# PowerManagement_Base.net
KiCad netlist of a schematic drawn in Altium Designer
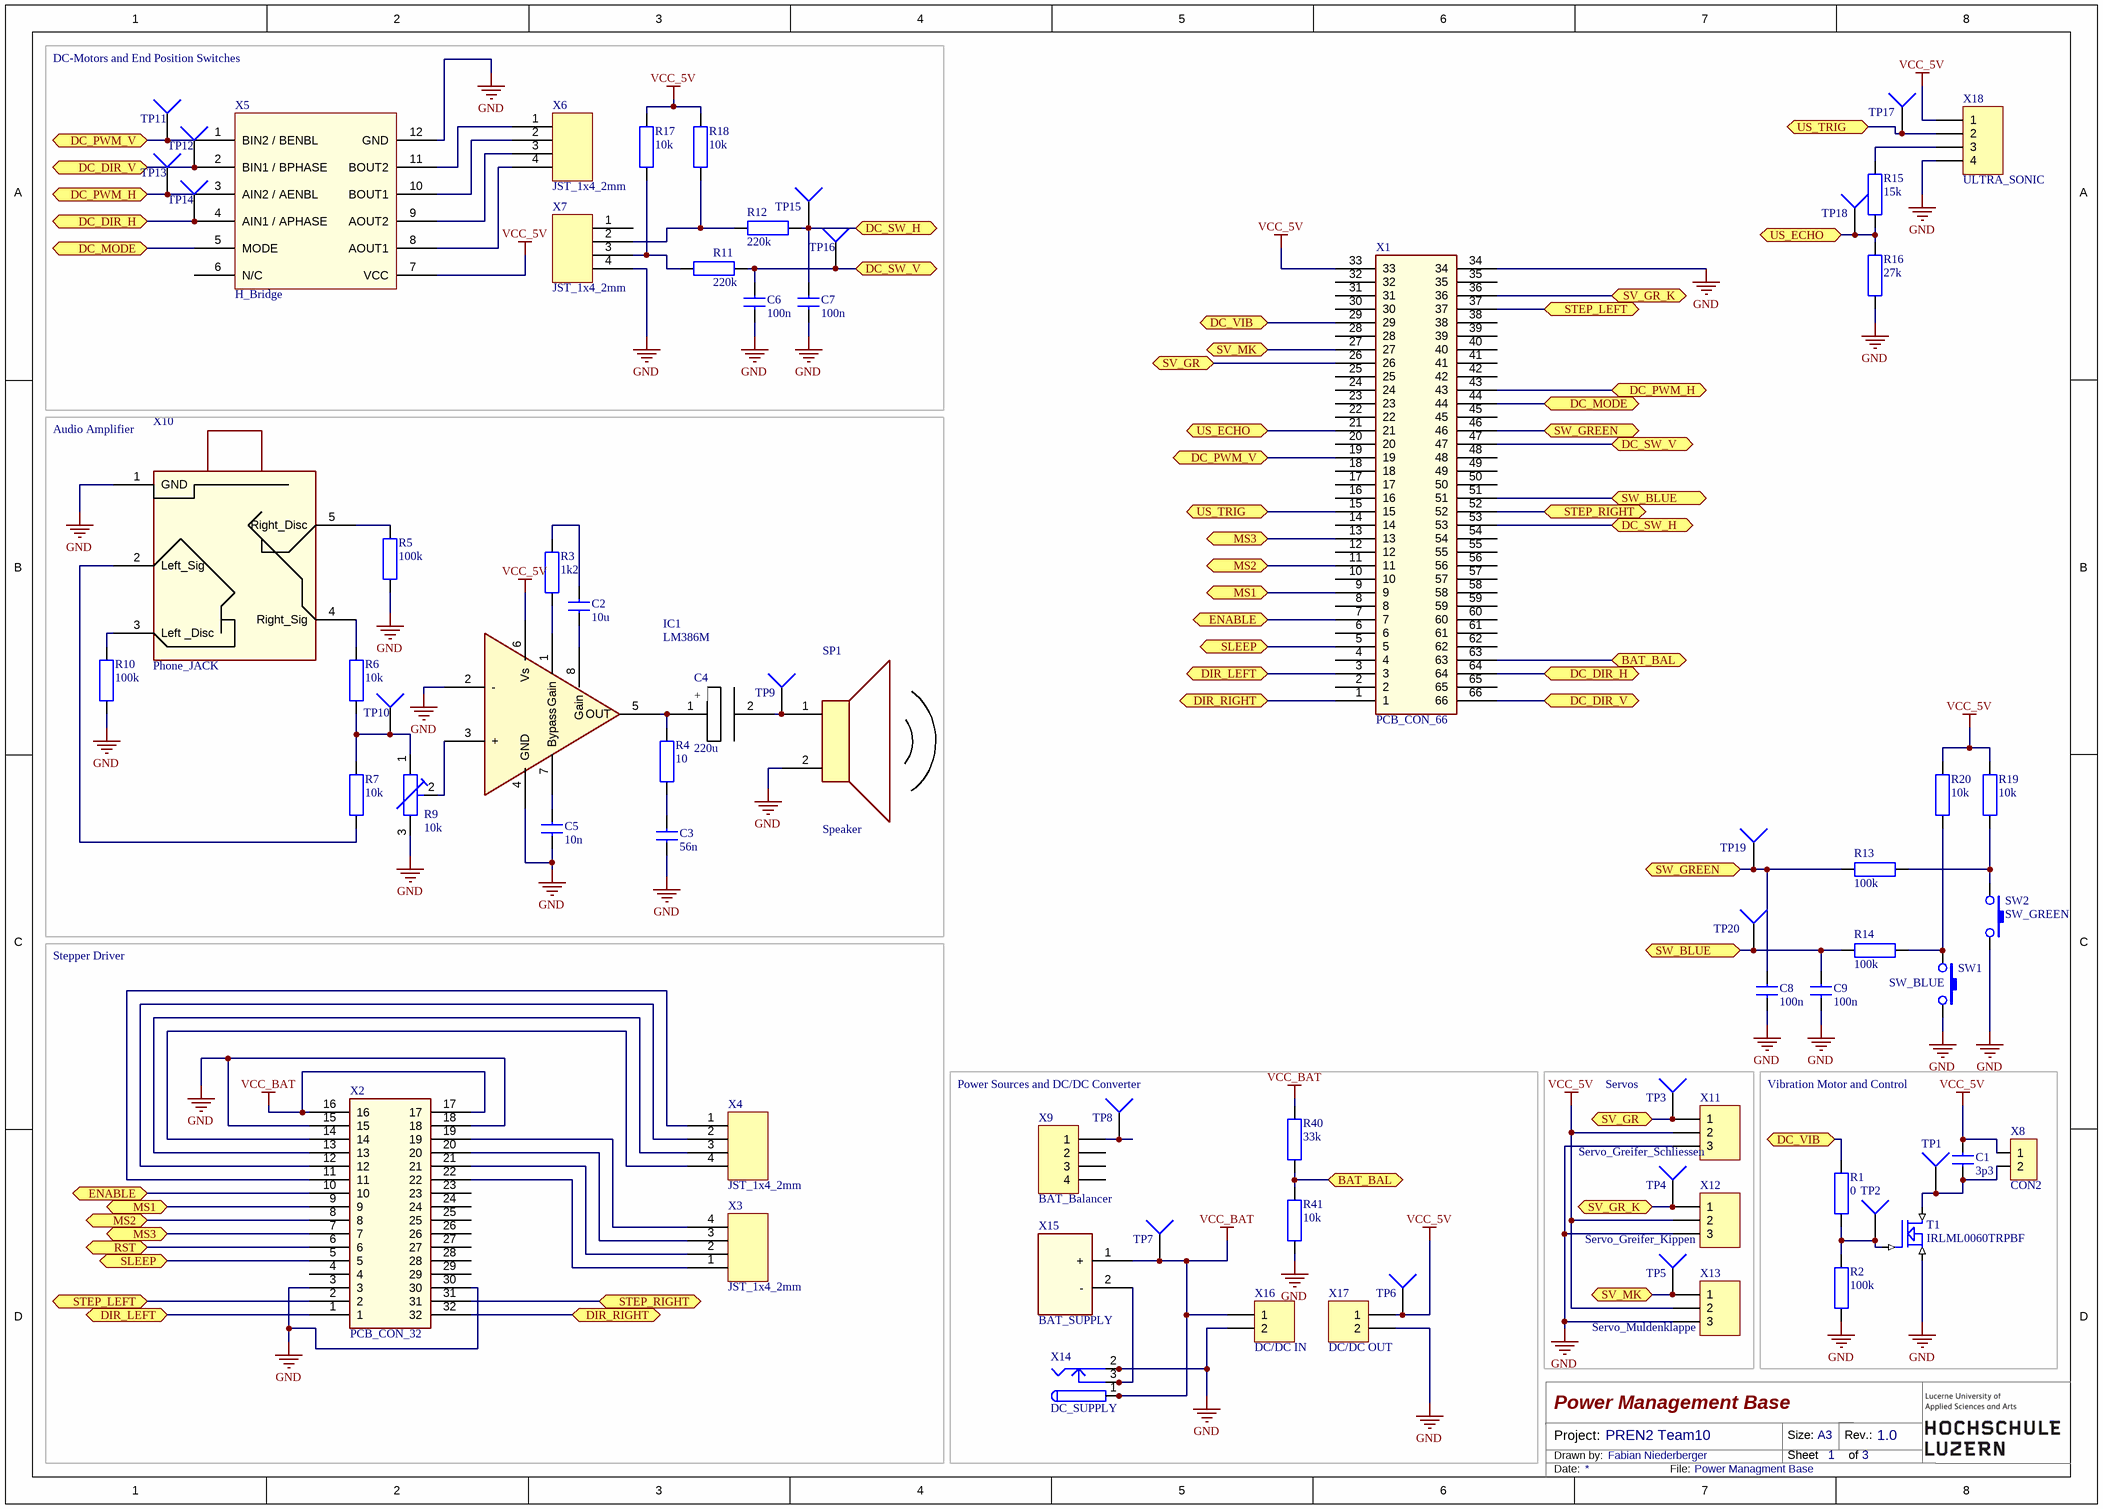
[diagram p0: PowerManagement_Base.SchDoc]

(export (version "E")
  (design (tool "Eeschema 10.0.6"))
  (components
    (comp (ref "C1")
      (value "3p3")
      (footprint "0805")
      (description "Normaler Kondensator")
      (libsource (lib "DEVICE_HSLU") (part "C?"))
    )
    (comp (ref "C2")
      (value "10u")
      (footprint "0805")
      (description "Normaler Kondensator")
      (libsource (lib "DEVICE_HSLU") (part "C?"))
    )
    (comp (ref "C3")
      (value "56n")
      (footprint "0805")
      (description "Normaler Kondensator")
      (libsource (lib "DEVICE_HSLU") (part "C?"))
    )
    (comp (ref "C4")
      (value "220u")
      (footprint "Elko")
      (description "Electrolyt Capacitor")
      (libsource (lib "PREN2Lib") (part "Elko"))
    )
    (comp (ref "C5")
      (value "10n")
      (footprint "0805")
      (description "Normaler Kondensator")
      (libsource (lib "DEVICE_HSLU") (part "C?"))
    )
    (comp (ref "C6")
      (value "100n")
      (footprint "0805")
      (description "Normaler Kondensator")
      (libsource (lib "DEVICE_HSLU") (part "C?"))
    )
    (comp (ref "C7")
      (value "100n")
      (footprint "0805")
      (description "Normaler Kondensator")
      (libsource (lib "DEVICE_HSLU") (part "C?"))
    )
    (comp (ref "C8")
      (value "100n")
      (footprint "0805")
      (description "Normaler Kondensator")
      (libsource (lib "DEVICE_HSLU") (part "C?"))
    )
    (comp (ref "C9")
      (value "100n")
      (footprint "0805")
      (description "Normaler Kondensator")
      (libsource (lib "DEVICE_HSLU") (part "C?"))
    )
    (comp (ref "IC1")
      (value "LM386M")
      (footprint "SO-8")
      (description "Audio AMP in SO-8 Package")
      (libsource (lib "PREN2Lib") (part "Audio Amp"))
    )
    (comp (ref "R1")
      (value "0")
      (footprint "0805")
      (description "Normaler Widerstand")
      (libsource (lib "DEVICE_HSLU") (part "R?"))
    )
    (comp (ref "R2")
      (value "100k")
      (footprint "0805")
      (description "Normaler Widerstand")
      (libsource (lib "DEVICE_HSLU") (part "R?"))
    )
    (comp (ref "R3")
      (value "1k2")
      (footprint "0805")
      (description "Normaler Widerstand")
      (libsource (lib "DEVICE_HSLU") (part "R?"))
    )
    (comp (ref "R4")
      (value "10")
      (footprint "0805")
      (description "Normaler Widerstand")
      (libsource (lib "DEVICE_HSLU") (part "R?"))
    )
    (comp (ref "R5")
      (value "100k")
      (footprint "0805")
      (description "Normaler Widerstand")
      (libsource (lib "DEVICE_HSLU") (part "R?"))
    )
    (comp (ref "R6")
      (value "10k")
      (footprint "0805")
      (description "Normaler Widerstand")
      (libsource (lib "DEVICE_HSLU") (part "R?"))
    )
    (comp (ref "R7")
      (value "10k")
      (footprint "0805")
      (description "Normaler Widerstand")
      (libsource (lib "DEVICE_HSLU") (part "R?"))
    )
    (comp (ref "R9") (value "10k") (footprint "POT2") (libsource (lib "DEVICE_HSLU") (part "R_POT1")))
    (comp (ref "R10")
      (value "100k")
      (footprint "0805")
      (description "Normaler Widerstand")
      (libsource (lib "DEVICE_HSLU") (part "R?"))
    )
    (comp (ref "R11")
      (value "220k")
      (footprint "0805")
      (description "Normaler Widerstand")
      (libsource (lib "DEVICE_HSLU") (part "R?"))
    )
    (comp (ref "R12")
      (value "220k")
      (footprint "0805")
      (description "Normaler Widerstand")
      (libsource (lib "DEVICE_HSLU") (part "R?"))
    )
    (comp (ref "R13")
      (value "100k")
      (footprint "0805")
      (description "Normaler Widerstand")
      (libsource (lib "DEVICE_HSLU") (part "R?"))
    )
    (comp (ref "R14")
      (value "100k")
      (footprint "0805")
      (description "Normaler Widerstand")
      (libsource (lib "DEVICE_HSLU") (part "R?"))
    )
    (comp (ref "R15")
      (value "15k")
      (footprint "0805")
      (description "Normaler Widerstand")
      (libsource (lib "DEVICE_HSLU") (part "R?"))
    )
    (comp (ref "R16")
      (value "27k")
      (footprint "0805")
      (description "Normaler Widerstand")
      (libsource (lib "DEVICE_HSLU") (part "R?"))
    )
    (comp (ref "R17")
      (value "10k")
      (footprint "0805")
      (description "Normaler Widerstand")
      (libsource (lib "DEVICE_HSLU") (part "R?"))
    )
    (comp (ref "R18")
      (value "10k")
      (footprint "0805")
      (description "Normaler Widerstand")
      (libsource (lib "DEVICE_HSLU") (part "R?"))
    )
    (comp (ref "R19")
      (value "10k")
      (footprint "0805")
      (description "Normaler Widerstand")
      (libsource (lib "DEVICE_HSLU") (part "R?"))
    )
    (comp (ref "R20")
      (value "10k")
      (footprint "0805")
      (description "Normaler Widerstand")
      (libsource (lib "DEVICE_HSLU") (part "R?"))
    )
    (comp (ref "R40")
      (value "33k")
      (footprint "0805")
      (description "Normaler Widerstand")
      (libsource (lib "DEVICE_HSLU") (part "R?"))
    )
    (comp (ref "R41")
      (value "10k")
      (footprint "0805")
      (description "Normaler Widerstand")
      (libsource (lib "DEVICE_HSLU") (part "R?"))
    )
    (comp (ref "SP1")
      (value "Speaker")
      (footprint "Speaker")
      (description "8 Ohm Speaker")
      (libsource (lib "PREN2Lib") (part "Speaker"))
    )
    (comp (ref "SW1") (value "SW_BLUE") (footprint "TASTER") (libsource (lib "DEVICE_HSLU") (part "SW-PB")))
    (comp (ref "SW2") (value "SW_GREEN") (footprint "TASTER") (libsource (lib "DEVICE_HSLU") (part "SW-PB")))
    (comp (ref "T1")
      (value "IRLML0060TRPBF")
      (footprint "SOT-23")
      (libsource (lib "DEVICE_HSLU") (part "MOSFET N"))
    )
    (comp (ref "TP1")
      (value "~")
      (footprint "PIN1")
      (fields (field (name "PUBLISHER") "Altium Limited"))
      (libsource (lib "Miscellaneous Connectors") (part "Socket"))
    )
    (comp (ref "TP2")
      (value "~")
      (footprint "PIN1")
      (fields (field (name "PUBLISHER") "Altium Limited"))
      (libsource (lib "Miscellaneous Connectors") (part "Socket"))
    )
    (comp (ref "TP3")
      (value "~")
      (footprint "PIN1")
      (fields (field (name "PUBLISHER") "Altium Limited"))
      (libsource (lib "Miscellaneous Connectors") (part "Socket"))
    )
    (comp (ref "TP4")
      (value "~")
      (footprint "PIN1")
      (fields (field (name "PUBLISHER") "Altium Limited"))
      (libsource (lib "Miscellaneous Connectors") (part "Socket"))
    )
    (comp (ref "TP5")
      (value "~")
      (footprint "PIN1")
      (fields (field (name "PUBLISHER") "Altium Limited"))
      (libsource (lib "Miscellaneous Connectors") (part "Socket"))
    )
    (comp (ref "TP6")
      (value "~")
      (footprint "PIN1")
      (fields (field (name "PUBLISHER") "Altium Limited"))
      (libsource (lib "Miscellaneous Connectors") (part "Socket"))
    )
    (comp (ref "TP7")
      (value "~")
      (footprint "PIN1")
      (fields (field (name "PUBLISHER") "Altium Limited"))
      (libsource (lib "Miscellaneous Connectors") (part "Socket"))
    )
    (comp (ref "TP8")
      (value "~")
      (footprint "PIN1")
      (fields (field (name "PUBLISHER") "Altium Limited"))
      (libsource (lib "Miscellaneous Connectors") (part "Socket"))
    )
    (comp (ref "TP9")
      (value "~")
      (footprint "PIN1")
      (fields (field (name "PUBLISHER") "Altium Limited"))
      (libsource (lib "Miscellaneous Connectors") (part "Socket"))
    )
    (comp (ref "TP10")
      (value "~")
      (footprint "PIN1")
      (fields (field (name "PUBLISHER") "Altium Limited"))
      (libsource (lib "Miscellaneous Connectors") (part "Socket"))
    )
    (comp (ref "TP11")
      (value "~")
      (footprint "PIN1")
      (fields (field (name "PUBLISHER") "Altium Limited"))
      (libsource (lib "Miscellaneous Connectors") (part "Socket"))
    )
    (comp (ref "TP12")
      (value "~")
      (footprint "PIN1")
      (fields (field (name "PUBLISHER") "Altium Limited"))
      (libsource (lib "Miscellaneous Connectors") (part "Socket"))
    )
    (comp (ref "TP13")
      (value "~")
      (footprint "PIN1")
      (fields (field (name "PUBLISHER") "Altium Limited"))
      (libsource (lib "Miscellaneous Connectors") (part "Socket"))
    )
    (comp (ref "TP14")
      (value "~")
      (footprint "PIN1")
      (fields (field (name "PUBLISHER") "Altium Limited"))
      (libsource (lib "Miscellaneous Connectors") (part "Socket"))
    )
    (comp (ref "TP15")
      (value "~")
      (footprint "PIN1")
      (fields (field (name "PUBLISHER") "Altium Limited"))
      (libsource (lib "Miscellaneous Connectors") (part "Socket"))
    )
    (comp (ref "TP16")
      (value "~")
      (footprint "PIN1")
      (fields (field (name "PUBLISHER") "Altium Limited"))
      (libsource (lib "Miscellaneous Connectors") (part "Socket"))
    )
    (comp (ref "TP17")
      (value "~")
      (footprint "PIN1")
      (fields (field (name "PUBLISHER") "Altium Limited"))
      (libsource (lib "Miscellaneous Connectors") (part "Socket"))
    )
    (comp (ref "TP18")
      (value "~")
      (footprint "PIN1")
      (fields (field (name "PUBLISHER") "Altium Limited"))
      (libsource (lib "Miscellaneous Connectors") (part "Socket"))
    )
    (comp (ref "TP19")
      (value "~")
      (footprint "PIN1")
      (fields (field (name "PUBLISHER") "Altium Limited"))
      (libsource (lib "Miscellaneous Connectors") (part "Socket"))
    )
    (comp (ref "TP20")
      (value "~")
      (footprint "PIN1")
      (fields (field (name "PUBLISHER") "Altium Limited"))
      (libsource (lib "Miscellaneous Connectors") (part "Socket"))
    )
    (comp (ref "X1")
      (value "PCB_CON_66")
      (footprint "PCB_CON_66_JACK")
      (description "Connects a PCB with another. This scheme is either jack or plug, depends on footprint")
      (libsource (lib "PREN2Lib") (part "PCB_CON_66"))
    )
    (comp (ref "X2")
      (value "PCB_CON_32")
      (footprint "PCB_CON_32_JACK")
      (description "Connects a PCB with another. This scheme is either jack or plug, depends on footprint")
      (libsource (lib "PREN2Lib") (part "PCB_CON_32"))
    )
    (comp (ref "X3")
      (value "JST_1x4_2mm")
      (footprint "JST_1x4_2mm_horizontal")
      (description "JST connector single row 4 pin, 2mm grid")
      (libsource (lib "") (part "JST_1x4_2mm_2"))
    )
    (comp (ref "X4")
      (value "JST_1x4_2mm")
      (footprint "JST_1x4_2mm_horizontal")
      (description "JST connector single row 4 pin, 2mm grid")
      (libsource (lib "PREN2Lib") (part "JST_1x4_2mm"))
    )
    (comp (ref "X5")
      (value "H_Bridge")
      (footprint "H_Bridge")
      (description "H-Bridge Shield")
      (libsource (lib "PREN2Lib") (part "H_Bridge"))
    )
    (comp (ref "X6")
      (value "JST_1x4_2mm")
      (footprint "JST_1x4_2mm_horizontal")
      (description "JST connector single row 4 pin, 2mm grid")
      (libsource (lib "PREN2Lib") (part "JST_1x4_2mm"))
    )
    (comp (ref "X7")
      (value "JST_1x4_2mm")
      (footprint "JST_1x4_2mm_horizontal")
      (description "JST connector single row 4 pin, 2mm grid")
      (libsource (lib "") (part "JST_1x4_2mm_1"))
    )
    (comp (ref "X8") (value "CON2") (footprint "HDR1X2") (libsource (lib "DEVICE_HSLU") (part "CON2")))
    (comp (ref "X9")
      (value "BAT_Balancer")
      (footprint "HDR1X4")
      (description "Header, 4-Pin")
      (fields (field (name "PUBLISHER") "Altium Limited"))
      (libsource (lib "") (part "Header 4_1"))
    )
    (comp (ref "X10")
      (value "Phone_JACK")
      (footprint "Audio_CON 3.5mm")
      (description "3.5 mm Phone Jack Stereo with Disconnect information")
      (libsource (lib "PREN2Lib") (part "Phone_JACK"))
    )
    (comp (ref "X11")
      (value "Servo_Greifer_Schliessen")
      (footprint "HDR1X3")
      (description "Header, 3-Pin")
      (fields (field (name "PUBLISHER") "Altium Limited"))
      (libsource (lib "Miscellaneous Connectors") (part "Header 3"))
    )
    (comp (ref "X12")
      (value "Servo_Greifer_Kippen")
      (footprint "HDR1X3")
      (description "Header, 3-Pin")
      (fields (field (name "PUBLISHER") "Altium Limited"))
      (libsource (lib "Miscellaneous Connectors") (part "Header 3"))
    )
    (comp (ref "X13")
      (value "Servo_Muldenklappe")
      (footprint "HDR1X3")
      (description "Header, 3-Pin")
      (fields (field (name "PUBLISHER") "Altium Limited"))
      (libsource (lib "Miscellaneous Connectors") (part "Header 3"))
    )
    (comp (ref "X14")
      (value "DC_SUPPLY")
      (footprint "KLD-0202")
      (description "Low Voltage Power Supply Connector")
      (fields (field (name "PUBLISHER") "Altium Limited"))
      (libsource (lib "Miscellaneous Connectors") (part "PWR2.5"))
    )
    (comp (ref "X15")
      (value "BAT_SUPPLY")
      (footprint "XT60_CON")
      (description "XT60 LiPo Accumulator Connector")
      (libsource (lib "PREN2Lib") (part "XT60_CON"))
    )
    (comp (ref "X16")
      (value "DC/DC IN")
      (footprint "HDR1X2H")
      (description "Header, 2-Pin, Right Angle")
      (fields (field (name "PUBLISHER") "Altium Limited"))
      (libsource (lib "") (part "Header 2H_1"))
    )
    (comp (ref "X17")
      (value "DC/DC OUT")
      (footprint "HDR1X2H")
      (description "Header, 2-Pin, Right Angle")
      (fields (field (name "PUBLISHER") "Altium Limited"))
      (libsource (lib "Miscellaneous Connectors") (part "Header 2H"))
    )
    (comp (ref "X18")
      (value "ULTRA_SONIC")
      (footprint "HDR1X4")
      (description "Header, 4-Pin")
      (fields (field (name "PUBLISHER") "Altium Limited"))
      (libsource (lib "Miscellaneous Connectors") (part "Header 4"))
    )
  )
  (nets
    (net (code "1") (name "/BAT_BAL") (class "Default")
      (node (ref "R40") (pin "1") (pintype "passive"))
      (node (ref "R41") (pin "2") (pintype "passive"))
      (node (ref "X1") (pin "63") (pinfunction "63_63") (pintype "passive"))
    )
    (net (code "2") (name "/DC_DIR_H") (class "Default")
      (node (ref "TP14") (pin "1") (pinfunction "1_1") (pintype "passive"))
      (node (ref "X1") (pin "64") (pinfunction "64_64") (pintype "passive"))
      (node (ref "X5") (pin "4") (pinfunction "AIN1_/_APHASE_4") (pintype "passive"))
    )
    (net (code "3") (name "/DC_DIR_V") (class "Default")
      (node (ref "TP12") (pin "1") (pinfunction "1_1") (pintype "passive"))
      (node (ref "X1") (pin "66") (pinfunction "66_66") (pintype "passive"))
      (node (ref "X5") (pin "2") (pinfunction "BIN1_/_BPHASE_2") (pintype "passive"))
    )
    (net (code "4") (name "/DC_MODE") (class "Default")
      (node (ref "X1") (pin "44") (pinfunction "44_44") (pintype "passive"))
      (node (ref "X5") (pin "5") (pinfunction "MODE_5") (pintype "passive"))
    )
    (net (code "5") (name "/DC_PWM_H") (class "Default")
      (node (ref "TP13") (pin "1") (pinfunction "1_1") (pintype "passive"))
      (node (ref "X1") (pin "43") (pinfunction "43_43") (pintype "passive"))
      (node (ref "X5") (pin "3") (pinfunction "AIN2_/_AENBL_3") (pintype "passive"))
    )
    (net (code "6") (name "/DC_PWM_V") (class "Default")
      (node (ref "TP11") (pin "1") (pinfunction "1_1") (pintype "passive"))
      (node (ref "X1") (pin "19") (pinfunction "19_19") (pintype "passive"))
      (node (ref "X5") (pin "1") (pinfunction "BIN2_/_BENBL_1") (pintype "passive"))
    )
    (net (code "7") (name "/DC_SW_H") (class "Default")
      (node (ref "C7") (pin "1") (pinfunction "1_1") (pintype "passive"))
      (node (ref "R12") (pin "2") (pintype "passive"))
      (node (ref "TP15") (pin "1") (pinfunction "1_1") (pintype "passive"))
      (node (ref "X1") (pin "53") (pinfunction "53_53") (pintype "passive"))
    )
    (net (code "8") (name "/DC_SW_V") (class "Default")
      (node (ref "C6") (pin "1") (pinfunction "1_1") (pintype "passive"))
      (node (ref "R11") (pin "2") (pintype "passive"))
      (node (ref "TP16") (pin "1") (pinfunction "1_1") (pintype "passive"))
      (node (ref "X1") (pin "47") (pinfunction "47_47") (pintype "passive"))
    )
    (net (code "9") (name "/DC_VIB") (class "Default")
      (node (ref "R1") (pin "2") (pintype "passive"))
      (node (ref "X1") (pin "29") (pinfunction "29_29") (pintype "passive"))
    )
    (net (code "10") (name "/DIR_LEFT") (class "Default")
      (node (ref "X1") (pin "3") (pinfunction "3_3") (pintype "passive"))
      (node (ref "X2") (pin "1") (pinfunction "1_1") (pintype "passive"))
    )
    (net (code "11") (name "/DIR_RIGHT") (class "Default")
      (node (ref "X1") (pin "1") (pinfunction "1_1") (pintype "passive"))
      (node (ref "X2") (pin "32") (pinfunction "32_32") (pintype "passive"))
    )
    (net (code "12") (name "/ENABLE") (class "Default")
      (node (ref "X1") (pin "7") (pinfunction "7_7") (pintype "passive"))
      (node (ref "X2") (pin "10") (pinfunction "10_10") (pintype "passive"))
    )
    (net (code "13") (name "/MS1") (class "Default")
      (node (ref "X1") (pin "9") (pinfunction "9_9") (pintype "passive"))
      (node (ref "X2") (pin "9") (pinfunction "9_9") (pintype "passive"))
    )
    (net (code "14") (name "/MS2") (class "Default")
      (node (ref "X1") (pin "11") (pinfunction "11_11") (pintype "passive"))
      (node (ref "X2") (pin "8") (pinfunction "8_8") (pintype "passive"))
    )
    (net (code "15") (name "/MS3") (class "Default")
      (node (ref "X1") (pin "13") (pinfunction "13_13") (pintype "passive"))
      (node (ref "X2") (pin "7") (pinfunction "7_7") (pintype "passive"))
    )
    (net (code "16") (name "/RST") (class "Default")
      (node (ref "X2") (pin "6") (pinfunction "6_6") (pintype "passive"))
    )
    (net (code "17") (name "/SLEEP") (class "Default")
      (node (ref "X1") (pin "5") (pinfunction "5_5") (pintype "passive"))
      (node (ref "X2") (pin "5") (pinfunction "5_5") (pintype "passive"))
    )
    (net (code "18") (name "/STEP_LEFT") (class "Default")
      (node (ref "X1") (pin "37") (pinfunction "37_37") (pintype "passive"))
      (node (ref "X2") (pin "2") (pinfunction "2_2") (pintype "passive"))
    )
    (net (code "19") (name "/STEP_RIGHT") (class "Default")
      (node (ref "X1") (pin "52") (pinfunction "52_52") (pintype "passive"))
      (node (ref "X2") (pin "31") (pinfunction "31_31") (pintype "passive"))
    )
    (net (code "20") (name "/SV_GR") (class "Default")
      (node (ref "TP3") (pin "1") (pinfunction "1_1") (pintype "passive"))
      (node (ref "X1") (pin "26") (pinfunction "26_26") (pintype "passive"))
      (node (ref "X11") (pin "1") (pinfunction "1_1") (pintype "passive"))
    )
    (net (code "21") (name "/SV_GR_K") (class "Default")
      (node (ref "TP4") (pin "1") (pinfunction "1_1") (pintype "passive"))
      (node (ref "X1") (pin "36") (pinfunction "36_36") (pintype "passive"))
      (node (ref "X12") (pin "1") (pinfunction "1_1") (pintype "passive"))
    )
    (net (code "22") (name "/SV_MK") (class "Default")
      (node (ref "TP5") (pin "1") (pinfunction "1_1") (pintype "passive"))
      (node (ref "X1") (pin "27") (pinfunction "27_27") (pintype "passive"))
      (node (ref "X13") (pin "1") (pinfunction "1_1") (pintype "passive"))
    )
    (net (code "23") (name "/SW_BLUE") (class "Default")
      (node (ref "C9") (pin "1") (pinfunction "1_1") (pintype "passive"))
      (node (ref "R14") (pin "1") (pintype "passive"))
      (node (ref "TP20") (pin "1") (pinfunction "1_1") (pintype "passive"))
      (node (ref "X1") (pin "51") (pinfunction "51_51") (pintype "passive"))
    )
    (net (code "24") (name "/SW_GREEN") (class "Default")
      (node (ref "C8") (pin "1") (pinfunction "1_1") (pintype "passive"))
      (node (ref "R13") (pin "1") (pintype "passive"))
      (node (ref "TP19") (pin "1") (pinfunction "1_1") (pintype "passive"))
      (node (ref "X1") (pin "46") (pinfunction "46_46") (pintype "passive"))
    )
    (net (code "25") (name "/US_ECHO") (class "Default")
      (node (ref "R15") (pin "1") (pintype "passive"))
      (node (ref "R16") (pin "2") (pintype "passive"))
      (node (ref "TP18") (pin "1") (pinfunction "1_1") (pintype "passive"))
      (node (ref "X1") (pin "21") (pinfunction "21_21") (pintype "passive"))
    )
    (net (code "26") (name "/US_TRIG") (class "Default")
      (node (ref "TP17") (pin "1") (pinfunction "1_1") (pintype "passive"))
      (node (ref "X1") (pin "15") (pinfunction "15_15") (pintype "passive"))
      (node (ref "X18") (pin "2") (pinfunction "2_2") (pintype "passive"))
    )
    (net (code "27") (name "GND") (class "Default")
      (node (ref "C3") (pin "2") (pinfunction "2_2") (pintype "passive"))
      (node (ref "C5") (pin "2") (pinfunction "2_2") (pintype "passive"))
      (node (ref "C6") (pin "2") (pinfunction "2_2") (pintype "passive"))
      (node (ref "C7") (pin "2") (pinfunction "2_2") (pintype "passive"))
      (node (ref "C8") (pin "2") (pinfunction "2_2") (pintype "passive"))
      (node (ref "C9") (pin "2") (pinfunction "2_2") (pintype "passive"))
      (node (ref "IC1") (pin "2") (pinfunction "-_2") (pintype "passive"))
      (node (ref "IC1") (pin "4") (pinfunction "GND_4") (pintype "passive"))
      (node (ref "R10") (pin "1") (pintype "passive"))
      (node (ref "R16") (pin "1") (pintype "passive"))
      (node (ref "R2") (pin "1") (pintype "passive"))
      (node (ref "R41") (pin "1") (pintype "passive"))
      (node (ref "R5") (pin "1") (pintype "passive"))
      (node (ref "R9") (pin "3") (pintype "passive"))
      (node (ref "SP1") (pin "2") (pinfunction "2_2") (pintype "passive"))
      (node (ref "SW1") (pin "2") (pintype "passive"))
      (node (ref "SW2") (pin "2") (pintype "passive"))
      (node (ref "T1") (pin "SOURCE") (pinfunction "SOURCE_SOURCE") (pintype "input"))
      (node (ref "X1") (pin "34") (pinfunction "34_34") (pintype "passive"))
      (node (ref "X10") (pin "1") (pinfunction "GND_1") (pintype "passive"))
      (node (ref "X11") (pin "3") (pinfunction "3_3") (pintype "passive"))
      (node (ref "X12") (pin "3") (pinfunction "3_3") (pintype "passive"))
      (node (ref "X13") (pin "3") (pinfunction "3_3") (pintype "passive"))
      (node (ref "X14") (pin "2") (pinfunction "2_2") (pintype "power_in"))
      (node (ref "X14") (pin "2A") (pinfunction "2A_2A") (pintype "power_in"))
      (node (ref "X14") (pin "2B") (pinfunction "2B_2B") (pintype "power_in"))
      (node (ref "X16") (pin "2") (pinfunction "2_2") (pintype "passive"))
      (node (ref "X17") (pin "2") (pinfunction "2_2") (pintype "passive"))
      (node (ref "X18") (pin "4") (pinfunction "4_4") (pintype "passive"))
      (node (ref "X2") (pin "15") (pinfunction "15_15") (pintype "passive"))
      (node (ref "X2") (pin "18") (pinfunction "18_18") (pintype "passive"))
      (node (ref "X2") (pin "3") (pinfunction "3_3") (pintype "passive"))
      (node (ref "X2") (pin "30") (pinfunction "30_30") (pintype "passive"))
      (node (ref "X5") (pin "12") (pinfunction "GND_12") (pintype "power_in"))
      (node (ref "X7") (pin "4") (pintype "passive"))
    )
    (net (code "28") (name "Net-(C1-Pad1)") (class "Default")
      (node (ref "C1") (pin "1") (pinfunction "1_1") (pintype "passive"))
      (node (ref "T1") (pin "DRAIN") (pinfunction "DRAIN_DRAIN") (pintype "input"))
      (node (ref "TP1") (pin "1") (pinfunction "1_1") (pintype "passive"))
      (node (ref "X8") (pin "2") (pinfunction "2_2") (pintype "passive"))
    )
    (net (code "29") (name "Net-(C2-Pad1)") (class "Default")
      (node (ref "C2") (pin "1") (pinfunction "1_1") (pintype "passive"))
      (node (ref "R3") (pin "2") (pintype "passive"))
    )
    (net (code "30") (name "Net-(C2-Pad2)") (class "Default")
      (node (ref "C2") (pin "2") (pinfunction "2_2") (pintype "passive"))
      (node (ref "IC1") (pin "8") (pinfunction "Gain_8") (pintype "passive"))
    )
    (net (code "31") (name "Net-(C3-Pad1)") (class "Default")
      (node (ref "C3") (pin "1") (pinfunction "1_1") (pintype "passive"))
      (node (ref "R4") (pin "1") (pintype "passive"))
    )
    (net (code "32") (name "Net-(C4-Pad2)") (class "Default")
      (node (ref "C4") (pin "2") (pintype "passive"))
      (node (ref "SP1") (pin "1") (pinfunction "1_1") (pintype "passive"))
      (node (ref "TP9") (pin "1") (pinfunction "1_1") (pintype "passive"))
    )
    (net (code "33") (name "Net-(IC1-+)") (class "Default")
      (node (ref "IC1") (pin "3") (pinfunction "+_3") (pintype "passive"))
      (node (ref "R9") (pin "2") (pintype "passive"))
    )
    (net (code "34") (name "Net-(IC1-Bypass)") (class "Default")
      (node (ref "C5") (pin "1") (pinfunction "1_1") (pintype "passive"))
      (node (ref "IC1") (pin "7") (pinfunction "Bypass_7") (pintype "passive"))
    )
    (net (code "35") (name "Net-(IC1-Gain-Pad1)") (class "Default")
      (node (ref "IC1") (pin "1") (pinfunction "Gain_1") (pintype "passive"))
      (node (ref "R3") (pin "1") (pintype "passive"))
    )
    (net (code "36") (name "Net-(IC1-OUT)") (class "Default")
      (node (ref "C4") (pin "1") (pintype "passive"))
      (node (ref "IC1") (pin "5") (pinfunction "OUT_5") (pintype "passive"))
      (node (ref "R4") (pin "2") (pintype "passive"))
    )
    (net (code "37") (name "Net-(R1-Pad1)") (class "Default")
      (node (ref "R1") (pin "1") (pintype "passive"))
      (node (ref "R2") (pin "2") (pintype "passive"))
      (node (ref "T1") (pin "GATE") (pinfunction "GATE_GATE") (pintype "input"))
      (node (ref "TP2") (pin "1") (pinfunction "1_1") (pintype "passive"))
    )
    (net (code "38") (name "Net-(R6-Pad2)") (class "Default")
      (node (ref "R6") (pin "2") (pintype "passive"))
      (node (ref "R7") (pin "1") (pintype "passive"))
      (node (ref "R9") (pin "1") (pintype "passive"))
      (node (ref "TP10") (pin "1") (pinfunction "1_1") (pintype "passive"))
    )
    (net (code "39") (name "Net-(R11-Pad1)") (class "Default")
      (node (ref "R11") (pin "1") (pintype "passive"))
      (node (ref "R17") (pin "1") (pintype "passive"))
      (node (ref "X7") (pin "3") (pintype "passive"))
    )
    (net (code "40") (name "Net-(R12-Pad1)") (class "Default")
      (node (ref "R12") (pin "1") (pintype "passive"))
      (node (ref "R18") (pin "1") (pintype "passive"))
      (node (ref "X7") (pin "2") (pintype "passive"))
    )
    (net (code "41") (name "Net-(R13-Pad2)") (class "Default")
      (node (ref "R13") (pin "2") (pintype "passive"))
      (node (ref "R19") (pin "2") (pintype "passive"))
      (node (ref "SW2") (pin "1") (pintype "passive"))
    )
    (net (code "42") (name "Net-(R14-Pad2)") (class "Default")
      (node (ref "R14") (pin "2") (pintype "passive"))
      (node (ref "R20") (pin "1") (pintype "passive"))
      (node (ref "SW1") (pin "1") (pintype "passive"))
    )
    (net (code "43") (name "Net-(R15-Pad2)") (class "Default")
      (node (ref "R15") (pin "2") (pintype "passive"))
      (node (ref "X18") (pin "3") (pinfunction "3_3") (pintype "passive"))
    )
    (net (code "44") (name "Net-(TP8-Pad1)") (class "Default")
      (node (ref "TP8") (pin "1") (pinfunction "1_1") (pintype "passive"))
      (node (ref "X9") (pin "1") (pinfunction "1_1") (pintype "passive"))
    )
    (net (code "45") (name "Net-(X2-Pad11)") (class "Default")
      (node (ref "X2") (pin "11") (pinfunction "11_11") (pintype "passive"))
      (node (ref "X4") (pin "1") (pintype "passive"))
    )
    (net (code "46") (name "Net-(X2-Pad12)") (class "Default")
      (node (ref "X2") (pin "12") (pinfunction "12_12") (pintype "passive"))
      (node (ref "X4") (pin "2") (pintype "passive"))
    )
    (net (code "47") (name "Net-(X2-Pad13)") (class "Default")
      (node (ref "X2") (pin "13") (pinfunction "13_13") (pintype "passive"))
      (node (ref "X4") (pin "3") (pintype "passive"))
    )
    (net (code "48") (name "Net-(X2-Pad14)") (class "Default")
      (node (ref "X2") (pin "14") (pinfunction "14_14") (pintype "passive"))
      (node (ref "X4") (pin "4") (pintype "passive"))
    )
    (net (code "49") (name "Net-(X2-Pad19)") (class "Default")
      (node (ref "X2") (pin "19") (pinfunction "19_19") (pintype "passive"))
      (node (ref "X3") (pin "4") (pintype "passive"))
    )
    (net (code "50") (name "Net-(X2-Pad20)") (class "Default")
      (node (ref "X2") (pin "20") (pinfunction "20_20") (pintype "passive"))
      (node (ref "X3") (pin "3") (pintype "passive"))
    )
    (net (code "51") (name "Net-(X2-Pad21)") (class "Default")
      (node (ref "X2") (pin "21") (pinfunction "21_21") (pintype "passive"))
      (node (ref "X3") (pin "2") (pintype "passive"))
    )
    (net (code "52") (name "Net-(X2-Pad22)") (class "Default")
      (node (ref "X2") (pin "22") (pinfunction "22_22") (pintype "passive"))
      (node (ref "X3") (pin "1") (pintype "passive"))
    )
    (net (code "53") (name "Net-(X5-AOUT1)") (class "Default")
      (node (ref "X5") (pin "8") (pinfunction "AOUT1_8") (pintype "passive"))
      (node (ref "X6") (pin "4") (pintype "passive"))
    )
    (net (code "54") (name "Net-(X5-AOUT2)") (class "Default")
      (node (ref "X5") (pin "9") (pinfunction "AOUT2_9") (pintype "passive"))
      (node (ref "X6") (pin "3") (pintype "passive"))
    )
    (net (code "55") (name "Net-(X5-BOUT1)") (class "Default")
      (node (ref "X5") (pin "10") (pinfunction "BOUT1_10") (pintype "passive"))
      (node (ref "X6") (pin "2") (pintype "passive"))
    )
    (net (code "56") (name "Net-(X5-BOUT2)") (class "Default")
      (node (ref "X5") (pin "11") (pinfunction "BOUT2_11") (pintype "passive"))
      (node (ref "X6") (pin "1") (pintype "passive"))
    )
    (net (code "57") (name "Net-(X10-Left_Sig)") (class "Default")
      (node (ref "R7") (pin "2") (pintype "passive"))
      (node (ref "X10") (pin "2") (pinfunction "Left_Sig_2") (pintype "passive"))
    )
    (net (code "58") (name "Net-(X10-Left__Disc)") (class "Default")
      (node (ref "R10") (pin "2") (pintype "passive"))
      (node (ref "X10") (pin "3") (pinfunction "Left__Disc_3") (pintype "passive"))
    )
    (net (code "59") (name "Net-(X10-Right_Disc)") (class "Default")
      (node (ref "R5") (pin "2") (pintype "passive"))
      (node (ref "X10") (pin "5") (pinfunction "Right_Disc_5") (pintype "passive"))
    )
    (net (code "60") (name "Net-(X10-Right_Sig)") (class "Default")
      (node (ref "R6") (pin "1") (pintype "passive"))
      (node (ref "X10") (pin "4") (pinfunction "Right_Sig_4") (pintype "passive"))
    )
    (net (code "61") (name "Net-(X15--)") (class "Default")
      (node (ref "X14") (pin "3") (pinfunction "3_3") (pintype "power_in"))
      (node (ref "X14") (pin "3A") (pinfunction "3A_3A") (pintype "power_in"))
      (node (ref "X14") (pin "3B") (pinfunction "3B_3B") (pintype "power_in"))
      (node (ref "X15") (pin "2") (pinfunction "-_2") (pintype "passive"))
    )
    (net (code "62") (name "VCC_5V") (class "Default")
      (node (ref "C1") (pin "2") (pinfunction "2_2") (pintype "passive"))
      (node (ref "IC1") (pin "6") (pinfunction "Vs_6") (pintype "passive"))
      (node (ref "R17") (pin "2") (pintype "passive"))
      (node (ref "R18") (pin "2") (pintype "passive"))
      (node (ref "R19") (pin "1") (pintype "passive"))
      (node (ref "R20") (pin "2") (pintype "passive"))
      (node (ref "TP6") (pin "1") (pinfunction "1_1") (pintype "passive"))
      (node (ref "X1") (pin "33") (pinfunction "33_33") (pintype "passive"))
      (node (ref "X11") (pin "2") (pinfunction "2_2") (pintype "passive"))
      (node (ref "X12") (pin "2") (pinfunction "2_2") (pintype "passive"))
      (node (ref "X13") (pin "2") (pinfunction "2_2") (pintype "passive"))
      (node (ref "X17") (pin "1") (pinfunction "1_1") (pintype "passive"))
      (node (ref "X18") (pin "1") (pinfunction "1_1") (pintype "passive"))
      (node (ref "X5") (pin "7") (pinfunction "VCC_7") (pintype "power_in"))
      (node (ref "X8") (pin "1") (pinfunction "1_1") (pintype "passive"))
    )
    (net (code "63") (name "VCC_BAT") (class "Default")
      (node (ref "R40") (pin "2") (pintype "passive"))
      (node (ref "TP7") (pin "1") (pinfunction "1_1") (pintype "passive"))
      (node (ref "X14") (pin "1") (pinfunction "1_1") (pintype "power_in"))
      (node (ref "X14") (pin "1A") (pinfunction "1A_1A") (pintype "power_in"))
      (node (ref "X14") (pin "1B") (pinfunction "1B_1B") (pintype "power_in"))
      (node (ref "X15") (pin "1") (pinfunction "+_1") (pintype "passive"))
      (node (ref "X16") (pin "1") (pinfunction "1_1") (pintype "passive"))
      (node (ref "X2") (pin "16") (pinfunction "16_16") (pintype "passive"))
      (node (ref "X2") (pin "17") (pinfunction "17_17") (pintype "passive"))
    )
    (net (code "64") (name "unconnected-(X1-Pad2)") (class "Default")
      (node (ref "X1") (pin "2") (pinfunction "2_2") (pintype "passive"))
    )
    (net (code "65") (name "unconnected-(X1-Pad4)") (class "Default")
      (node (ref "X1") (pin "4") (pinfunction "4_4") (pintype "passive"))
    )
    (net (code "66") (name "unconnected-(X1-Pad6)") (class "Default")
      (node (ref "X1") (pin "6") (pinfunction "6_6") (pintype "passive"))
    )
    (net (code "67") (name "unconnected-(X1-Pad8)") (class "Default")
      (node (ref "X1") (pin "8") (pinfunction "8_8") (pintype "passive"))
    )
    (net (code "68") (name "unconnected-(X1-Pad10)") (class "Default")
      (node (ref "X1") (pin "10") (pinfunction "10_10") (pintype "passive"))
    )
    (net (code "69") (name "unconnected-(X1-Pad12)") (class "Default")
      (node (ref "X1") (pin "12") (pinfunction "12_12") (pintype "passive"))
    )
    (net (code "70") (name "unconnected-(X1-Pad14)") (class "Default")
      (node (ref "X1") (pin "14") (pinfunction "14_14") (pintype "passive"))
    )
    (net (code "71") (name "unconnected-(X1-Pad16)") (class "Default")
      (node (ref "X1") (pin "16") (pinfunction "16_16") (pintype "passive"))
    )
    (net (code "72") (name "unconnected-(X1-Pad17)") (class "Default")
      (node (ref "X1") (pin "17") (pinfunction "17_17") (pintype "passive"))
    )
    (net (code "73") (name "unconnected-(X1-Pad18)") (class "Default")
      (node (ref "X1") (pin "18") (pinfunction "18_18") (pintype "passive"))
    )
    (net (code "74") (name "unconnected-(X1-Pad20)") (class "Default")
      (node (ref "X1") (pin "20") (pinfunction "20_20") (pintype "passive"))
    )
    (net (code "75") (name "unconnected-(X1-Pad22)") (class "Default")
      (node (ref "X1") (pin "22") (pinfunction "22_22") (pintype "passive"))
    )
    (net (code "76") (name "unconnected-(X1-Pad23)") (class "Default")
      (node (ref "X1") (pin "23") (pinfunction "23_23") (pintype "passive"))
    )
    (net (code "77") (name "unconnected-(X1-Pad24)") (class "Default")
      (node (ref "X1") (pin "24") (pinfunction "24_24") (pintype "passive"))
    )
    (net (code "78") (name "unconnected-(X1-Pad25)") (class "Default")
      (node (ref "X1") (pin "25") (pinfunction "25_25") (pintype "passive"))
    )
    (net (code "79") (name "unconnected-(X1-Pad28)") (class "Default")
      (node (ref "X1") (pin "28") (pinfunction "28_28") (pintype "passive"))
    )
    (net (code "80") (name "unconnected-(X1-Pad30)") (class "Default")
      (node (ref "X1") (pin "30") (pinfunction "30_30") (pintype "passive"))
    )
    (net (code "81") (name "unconnected-(X1-Pad31)") (class "Default")
      (node (ref "X1") (pin "31") (pinfunction "31_31") (pintype "passive"))
    )
    (net (code "82") (name "unconnected-(X1-Pad32)") (class "Default")
      (node (ref "X1") (pin "32") (pinfunction "32_32") (pintype "passive"))
    )
    (net (code "83") (name "unconnected-(X1-Pad35)") (class "Default")
      (node (ref "X1") (pin "35") (pinfunction "35_35") (pintype "passive"))
    )
    (net (code "84") (name "unconnected-(X1-Pad38)") (class "Default")
      (node (ref "X1") (pin "38") (pinfunction "38_38") (pintype "passive"))
    )
    (net (code "85") (name "unconnected-(X1-Pad39)") (class "Default")
      (node (ref "X1") (pin "39") (pinfunction "39_39") (pintype "passive"))
    )
    (net (code "86") (name "unconnected-(X1-Pad40)") (class "Default")
      (node (ref "X1") (pin "40") (pinfunction "40_40") (pintype "passive"))
    )
    (net (code "87") (name "unconnected-(X1-Pad41)") (class "Default")
      (node (ref "X1") (pin "41") (pinfunction "41_41") (pintype "passive"))
    )
    (net (code "88") (name "unconnected-(X1-Pad42)") (class "Default")
      (node (ref "X1") (pin "42") (pinfunction "42_42") (pintype "passive"))
    )
    (net (code "89") (name "unconnected-(X1-Pad45)") (class "Default")
      (node (ref "X1") (pin "45") (pinfunction "45_45") (pintype "passive"))
    )
    (net (code "90") (name "unconnected-(X1-Pad48)") (class "Default")
      (node (ref "X1") (pin "48") (pinfunction "48_48") (pintype "passive"))
    )
    (net (code "91") (name "unconnected-(X1-Pad49)") (class "Default")
      (node (ref "X1") (pin "49") (pinfunction "49_49") (pintype "passive"))
    )
    (net (code "92") (name "unconnected-(X1-Pad50)") (class "Default")
      (node (ref "X1") (pin "50") (pinfunction "50_50") (pintype "passive"))
    )
    (net (code "93") (name "unconnected-(X1-Pad54)") (class "Default")
      (node (ref "X1") (pin "54") (pinfunction "54_54") (pintype "passive"))
    )
    (net (code "94") (name "unconnected-(X1-Pad55)") (class "Default")
      (node (ref "X1") (pin "55") (pinfunction "55_55") (pintype "passive"))
    )
    (net (code "95") (name "unconnected-(X1-Pad56)") (class "Default")
      (node (ref "X1") (pin "56") (pinfunction "56_56") (pintype "passive"))
    )
    (net (code "96") (name "unconnected-(X1-Pad57)") (class "Default")
      (node (ref "X1") (pin "57") (pinfunction "57_57") (pintype "passive"))
    )
    (net (code "97") (name "unconnected-(X1-Pad58)") (class "Default")
      (node (ref "X1") (pin "58") (pinfunction "58_58") (pintype "passive"))
    )
    (net (code "98") (name "unconnected-(X1-Pad59)") (class "Default")
      (node (ref "X1") (pin "59") (pinfunction "59_59") (pintype "passive"))
    )
    (net (code "99") (name "unconnected-(X1-Pad60)") (class "Default")
      (node (ref "X1") (pin "60") (pinfunction "60_60") (pintype "passive"))
    )
    (net (code "100") (name "unconnected-(X1-Pad61)") (class "Default")
      (node (ref "X1") (pin "61") (pinfunction "61_61") (pintype "passive"))
    )
    (net (code "101") (name "unconnected-(X1-Pad62)") (class "Default")
      (node (ref "X1") (pin "62") (pinfunction "62_62") (pintype "passive"))
    )
    (net (code "102") (name "unconnected-(X1-Pad65)") (class "Default")
      (node (ref "X1") (pin "65") (pinfunction "65_65") (pintype "passive"))
    )
    (net (code "103") (name "unconnected-(X2-Pad4)") (class "Default")
      (node (ref "X2") (pin "4") (pinfunction "4_4") (pintype "passive"))
    )
    (net (code "104") (name "unconnected-(X2-Pad23)") (class "Default")
      (node (ref "X2") (pin "23") (pinfunction "23_23") (pintype "passive"))
    )
    (net (code "105") (name "unconnected-(X2-Pad24)") (class "Default")
      (node (ref "X2") (pin "24") (pinfunction "24_24") (pintype "passive"))
    )
    (net (code "106") (name "unconnected-(X2-Pad25)") (class "Default")
      (node (ref "X2") (pin "25") (pinfunction "25_25") (pintype "passive"))
    )
    (net (code "107") (name "unconnected-(X2-Pad26)") (class "Default")
      (node (ref "X2") (pin "26") (pinfunction "26_26") (pintype "passive"))
    )
    (net (code "108") (name "unconnected-(X2-Pad27)") (class "Default")
      (node (ref "X2") (pin "27") (pinfunction "27_27") (pintype "passive"))
    )
    (net (code "109") (name "unconnected-(X2-Pad28)") (class "Default")
      (node (ref "X2") (pin "28") (pinfunction "28_28") (pintype "passive"))
    )
    (net (code "110") (name "unconnected-(X2-Pad29)") (class "Default")
      (node (ref "X2") (pin "29") (pinfunction "29_29") (pintype "passive"))
    )
    (net (code "111") (name "unconnected-(X5-N{slash}C-Pad6)") (class "Default")
      (node (ref "X5") (pin "6") (pinfunction "N/C_6") (pintype "passive"))
    )
    (net (code "112") (name "unconnected-(X7-Pad1)") (class "Default")
      (node (ref "X7") (pin "1") (pintype "passive"))
    )
    (net (code "113") (name "unconnected-(X9-Pad2)") (class "Default")
      (node (ref "X9") (pin "2") (pinfunction "2_2") (pintype "passive"))
    )
    (net (code "114") (name "unconnected-(X9-Pad3)") (class "Default")
      (node (ref "X9") (pin "3") (pinfunction "3_3") (pintype "passive"))
    )
    (net (code "115") (name "unconnected-(X9-Pad4)") (class "Default")
      (node (ref "X9") (pin "4") (pinfunction "4_4") (pintype "passive"))
    )
  )
)
